# power_9v_rail.net
KiCad netlist of a schematic drawn in EAGLE
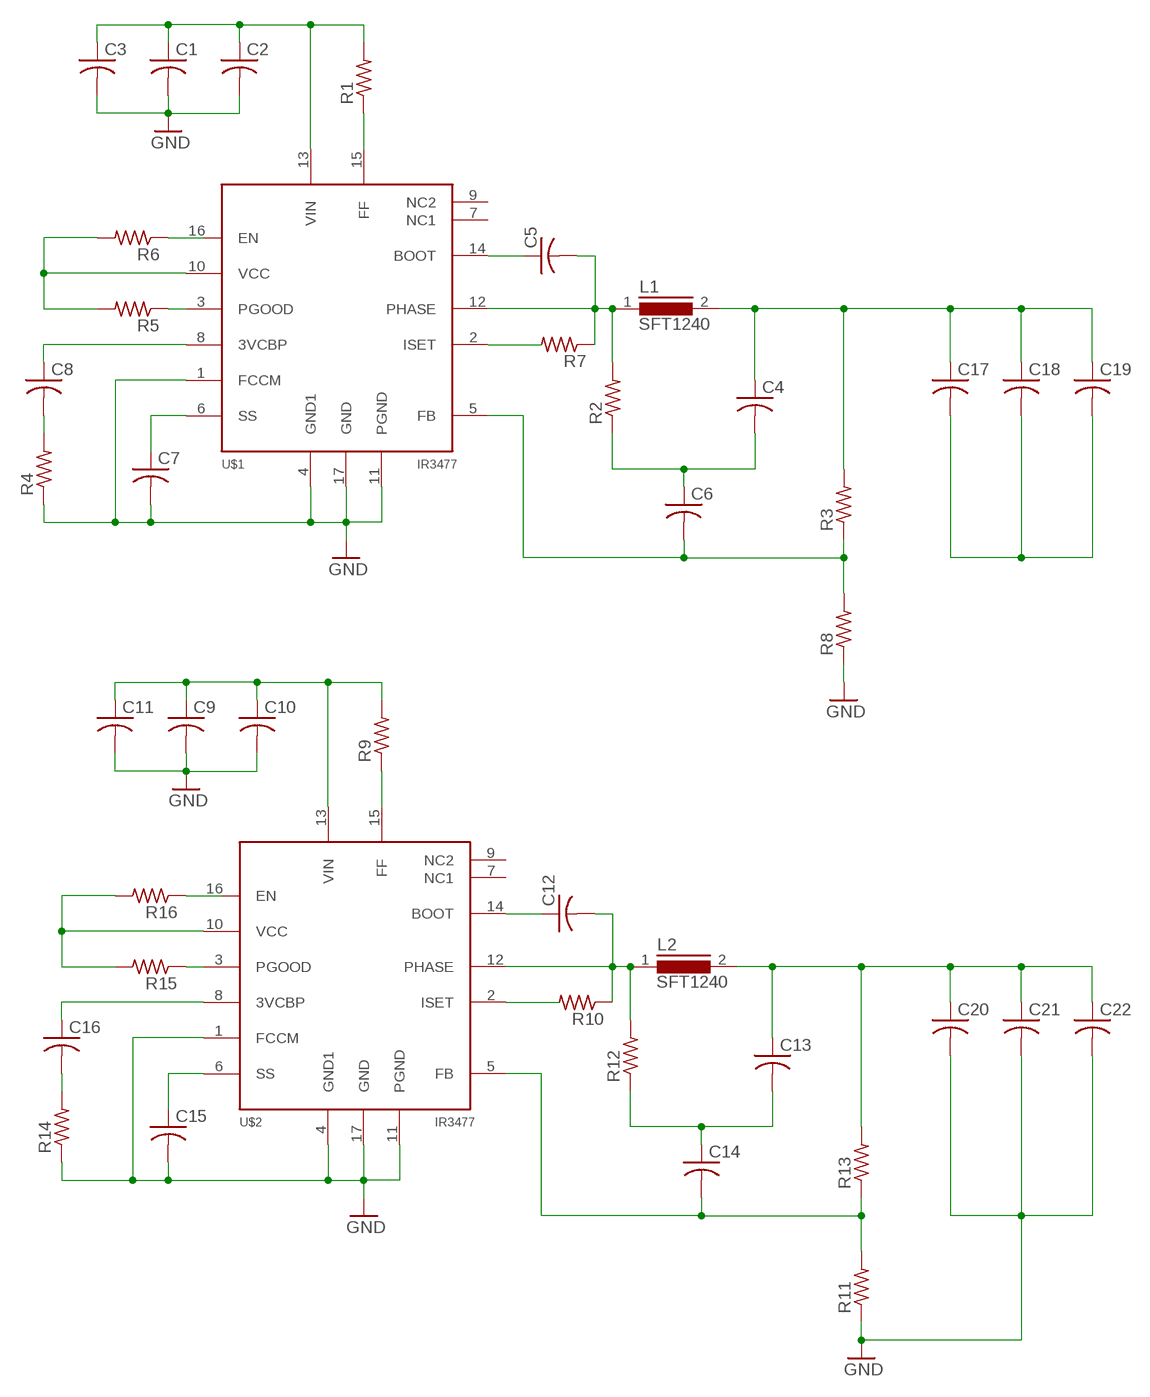
[diagram p0: schematic, sheet 1]

(export (version "E")
  (design (tool "Eeschema 10.0.6"))
  (components
    (comp (ref "C1")
      (value "C-USC0805K")
      (footprint "eagle-import:C0805K")
      (libsource (lib "eagle-import") (part "C-USC0805K"))
    )
    (comp (ref "C2")
      (value "C-USC0805K")
      (footprint "eagle-import:C0805K")
      (libsource (lib "eagle-import") (part "C-USC0805K"))
    )
    (comp (ref "C3")
      (value "C-USC0805K")
      (footprint "eagle-import:C0805K")
      (libsource (lib "eagle-import") (part "C-USC0805K"))
    )
    (comp (ref "C4")
      (value "C-USC0805K")
      (footprint "eagle-import:C0805K")
      (libsource (lib "eagle-import") (part "C-USC0805K"))
    )
    (comp (ref "C5")
      (value "C-USC0805K")
      (footprint "eagle-import:C0805K")
      (libsource (lib "eagle-import") (part "C-USC0805K"))
    )
    (comp (ref "C6")
      (value "C-USC0805K")
      (footprint "eagle-import:C0805K")
      (libsource (lib "eagle-import") (part "C-USC0805K"))
    )
    (comp (ref "C7")
      (value "C-USC0805K")
      (footprint "eagle-import:C0805K")
      (libsource (lib "eagle-import") (part "C-USC0805K"))
    )
    (comp (ref "C8")
      (value "C-USC0805K")
      (footprint "eagle-import:C0805K")
      (libsource (lib "eagle-import") (part "C-USC0805K"))
    )
    (comp (ref "C9")
      (value "C-USC0805K")
      (footprint "eagle-import:C0805K")
      (libsource (lib "eagle-import") (part "C-USC0805K"))
    )
    (comp (ref "C10")
      (value "C-USC0805K")
      (footprint "eagle-import:C0805K")
      (libsource (lib "eagle-import") (part "C-USC0805K"))
    )
    (comp (ref "C11")
      (value "C-USC0805K")
      (footprint "eagle-import:C0805K")
      (libsource (lib "eagle-import") (part "C-USC0805K"))
    )
    (comp (ref "C12")
      (value "C-USC0805K")
      (footprint "eagle-import:C0805K")
      (libsource (lib "eagle-import") (part "C-USC0805K"))
    )
    (comp (ref "C13")
      (value "C-USC0805K")
      (footprint "eagle-import:C0805K")
      (libsource (lib "eagle-import") (part "C-USC0805K"))
    )
    (comp (ref "C14")
      (value "C-USC0805K")
      (footprint "eagle-import:C0805K")
      (libsource (lib "eagle-import") (part "C-USC0805K"))
    )
    (comp (ref "C15")
      (value "C-USC0805K")
      (footprint "eagle-import:C0805K")
      (libsource (lib "eagle-import") (part "C-USC0805K"))
    )
    (comp (ref "C16")
      (value "C-USC0805K")
      (footprint "eagle-import:C0805K")
      (libsource (lib "eagle-import") (part "C-USC0805K"))
    )
    (comp (ref "C17")
      (value "C-USC0805K")
      (footprint "eagle-import:C0805K")
      (libsource (lib "eagle-import") (part "C-USC0805K"))
    )
    (comp (ref "C18")
      (value "C-USC0805K")
      (footprint "eagle-import:C0805K")
      (libsource (lib "eagle-import") (part "C-USC0805K"))
    )
    (comp (ref "C19")
      (value "C-USC0805K")
      (footprint "eagle-import:C0805K")
      (libsource (lib "eagle-import") (part "C-USC0805K"))
    )
    (comp (ref "C20")
      (value "C-USC0805K")
      (footprint "eagle-import:C0805K")
      (libsource (lib "eagle-import") (part "C-USC0805K"))
    )
    (comp (ref "C21")
      (value "C-USC0805K")
      (footprint "eagle-import:C0805K")
      (libsource (lib "eagle-import") (part "C-USC0805K"))
    )
    (comp (ref "C22")
      (value "C-USC0805K")
      (footprint "eagle-import:C0805K")
      (libsource (lib "eagle-import") (part "C-USC0805K"))
    )
    (comp (ref "L1")
      (value "SFT1240")
      (footprint "eagle-import:SFT1240")
      (libsource (lib "eagle-import") (part "SFT1240"))
    )
    (comp (ref "L2")
      (value "SFT1240")
      (footprint "eagle-import:SFT1240")
      (libsource (lib "eagle-import") (part "SFT1240"))
    )
    (comp (ref "R1")
      (value "R-US_R0805")
      (footprint "eagle-import:R0805")
      (libsource (lib "eagle-import") (part "R-US_R0805"))
    )
    (comp (ref "R2")
      (value "R-US_R0805")
      (footprint "eagle-import:R0805")
      (libsource (lib "eagle-import") (part "R-US_R0805"))
    )
    (comp (ref "R3")
      (value "R-US_R0805")
      (footprint "eagle-import:R0805")
      (libsource (lib "eagle-import") (part "R-US_R0805"))
    )
    (comp (ref "R4")
      (value "R-US_R0805")
      (footprint "eagle-import:R0805")
      (libsource (lib "eagle-import") (part "R-US_R0805"))
    )
    (comp (ref "R5")
      (value "R-US_R0805")
      (footprint "eagle-import:R0805")
      (libsource (lib "eagle-import") (part "R-US_R0805"))
    )
    (comp (ref "R6")
      (value "R-US_R0805")
      (footprint "eagle-import:R0805")
      (libsource (lib "eagle-import") (part "R-US_R0805"))
    )
    (comp (ref "R7")
      (value "R-US_R0805")
      (footprint "eagle-import:R0805")
      (libsource (lib "eagle-import") (part "R-US_R0805"))
    )
    (comp (ref "R8")
      (value "R-US_R0805")
      (footprint "eagle-import:R0805")
      (libsource (lib "eagle-import") (part "R-US_R0805"))
    )
    (comp (ref "R9")
      (value "R-US_R0805")
      (footprint "eagle-import:R0805")
      (libsource (lib "eagle-import") (part "R-US_R0805"))
    )
    (comp (ref "R10")
      (value "R-US_R0805")
      (footprint "eagle-import:R0805")
      (libsource (lib "eagle-import") (part "R-US_R0805"))
    )
    (comp (ref "R11")
      (value "R-US_R0805")
      (footprint "eagle-import:R0805")
      (libsource (lib "eagle-import") (part "R-US_R0805"))
    )
    (comp (ref "R12")
      (value "R-US_R0805")
      (footprint "eagle-import:R0805")
      (libsource (lib "eagle-import") (part "R-US_R0805"))
    )
    (comp (ref "R13")
      (value "R-US_R0805")
      (footprint "eagle-import:R0805")
      (libsource (lib "eagle-import") (part "R-US_R0805"))
    )
    (comp (ref "R14")
      (value "R-US_R0805")
      (footprint "eagle-import:R0805")
      (libsource (lib "eagle-import") (part "R-US_R0805"))
    )
    (comp (ref "R15")
      (value "R-US_R0805")
      (footprint "eagle-import:R0805")
      (libsource (lib "eagle-import") (part "R-US_R0805"))
    )
    (comp (ref "R16")
      (value "R-US_R0805")
      (footprint "eagle-import:R0805")
      (libsource (lib "eagle-import") (part "R-US_R0805"))
    )
    (comp (ref "U$1")
      (value "IC-1R34477-SMP")
      (footprint "eagle-import:IC-IR3477-SM")
      (libsource (lib "eagle-import") (part "IC-1R34477-SMP"))
    )
    (comp (ref "U$2")
      (value "IC-1R34477-SMP")
      (footprint "eagle-import:IC-IR3477-SM")
      (libsource (lib "eagle-import") (part "IC-1R34477-SMP"))
    )
  )
  (nets
    (net (code "1") (name "GND") (class "Default")
      (node (ref "C1") (pin "2") (pinfunction "2_2") (pintype "passive"))
      (node (ref "C10") (pin "2") (pinfunction "2_2") (pintype "passive"))
      (node (ref "C11") (pin "2") (pinfunction "2_2") (pintype "passive"))
      (node (ref "C15") (pin "2") (pinfunction "2_2") (pintype "passive"))
      (node (ref "C2") (pin "2") (pinfunction "2_2") (pintype "passive"))
      (node (ref "C20") (pin "2") (pinfunction "2_2") (pintype "passive"))
      (node (ref "C21") (pin "2") (pinfunction "2_2") (pintype "passive"))
      (node (ref "C22") (pin "2") (pinfunction "2_2") (pintype "passive"))
      (node (ref "C3") (pin "2") (pinfunction "2_2") (pintype "passive"))
      (node (ref "C7") (pin "2") (pinfunction "2_2") (pintype "passive"))
      (node (ref "C9") (pin "2") (pinfunction "2_2") (pintype "passive"))
      (node (ref "R11") (pin "1") (pinfunction "1_1") (pintype "passive"))
      (node (ref "R14") (pin "1") (pinfunction "1_1") (pintype "passive"))
      (node (ref "R4") (pin "1") (pinfunction "1_1") (pintype "passive"))
      (node (ref "R8") (pin "1") (pinfunction "1_1") (pintype "passive"))
      (node (ref "U$1") (pin "1") (pinfunction "FCCM_1") (pintype "bidirectional"))
      (node (ref "U$1") (pin "11") (pinfunction "PGND_11") (pintype "bidirectional"))
      (node (ref "U$1") (pin "17") (pinfunction "GND_17") (pintype "bidirectional"))
      (node (ref "U$1") (pin "4") (pinfunction "GND1_4") (pintype "bidirectional"))
      (node (ref "U$2") (pin "1") (pinfunction "FCCM_1") (pintype "bidirectional"))
      (node (ref "U$2") (pin "11") (pinfunction "PGND_11") (pintype "bidirectional"))
      (node (ref "U$2") (pin "17") (pinfunction "GND_17") (pintype "bidirectional"))
      (node (ref "U$2") (pin "4") (pinfunction "GND1_4") (pintype "bidirectional"))
    )
    (net (code "2") (name "Net-(C4-Pad2)") (class "Default")
      (node (ref "C4") (pin "2") (pinfunction "2_2") (pintype "passive"))
      (node (ref "C6") (pin "1") (pinfunction "1_1") (pintype "passive"))
      (node (ref "R2") (pin "1") (pinfunction "1_1") (pintype "passive"))
    )
    (net (code "3") (name "Net-(C8-Pad2)") (class "Default")
      (node (ref "C8") (pin "2") (pinfunction "2_2") (pintype "passive"))
      (node (ref "R4") (pin "2") (pinfunction "2_2") (pintype "passive"))
    )
    (net (code "4") (name "Net-(C13-Pad1)") (class "Default")
      (node (ref "C13") (pin "1") (pinfunction "1_1") (pintype "passive"))
      (node (ref "C20") (pin "1") (pinfunction "1_1") (pintype "passive"))
      (node (ref "C21") (pin "1") (pinfunction "1_1") (pintype "passive"))
      (node (ref "C22") (pin "1") (pinfunction "1_1") (pintype "passive"))
      (node (ref "L2") (pin "2") (pinfunction "2_2") (pintype "passive"))
      (node (ref "R13") (pin "2") (pinfunction "2_2") (pintype "passive"))
    )
    (net (code "5") (name "Net-(C13-Pad2)") (class "Default")
      (node (ref "C13") (pin "2") (pinfunction "2_2") (pintype "passive"))
      (node (ref "C14") (pin "1") (pinfunction "1_1") (pintype "passive"))
      (node (ref "R12") (pin "1") (pinfunction "1_1") (pintype "passive"))
    )
    (net (code "6") (name "Net-(C16-Pad2)") (class "Default")
      (node (ref "C16") (pin "2") (pinfunction "2_2") (pintype "passive"))
      (node (ref "R14") (pin "2") (pinfunction "2_2") (pintype "passive"))
    )
    (net (code "7") (name "Net-(C17-Pad1)") (class "Default")
      (node (ref "C17") (pin "1") (pinfunction "1_1") (pintype "passive"))
      (node (ref "C18") (pin "1") (pinfunction "1_1") (pintype "passive"))
      (node (ref "C19") (pin "1") (pinfunction "1_1") (pintype "passive"))
      (node (ref "C4") (pin "1") (pinfunction "1_1") (pintype "passive"))
      (node (ref "L1") (pin "2") (pinfunction "2_2") (pintype "passive"))
      (node (ref "R3") (pin "2") (pinfunction "2_2") (pintype "passive"))
    )
    (net (code "8") (name "Net-(C17-Pad2)") (class "Default")
      (node (ref "C17") (pin "2") (pinfunction "2_2") (pintype "passive"))
      (node (ref "C18") (pin "2") (pinfunction "2_2") (pintype "passive"))
      (node (ref "C19") (pin "2") (pinfunction "2_2") (pintype "passive"))
    )
    (net (code "9") (name "Net-(U$1-3VCBP)") (class "Default")
      (node (ref "C8") (pin "1") (pinfunction "1_1") (pintype "passive"))
      (node (ref "U$1") (pin "8") (pinfunction "3VCBP_8") (pintype "bidirectional"))
    )
    (net (code "10") (name "Net-(U$1-BOOT)") (class "Default")
      (node (ref "C5") (pin "1") (pinfunction "1_1") (pintype "passive"))
      (node (ref "U$1") (pin "14") (pinfunction "BOOT_14") (pintype "bidirectional"))
    )
    (net (code "11") (name "Net-(U$1-FB)") (class "Default")
      (node (ref "C6") (pin "2") (pinfunction "2_2") (pintype "passive"))
      (node (ref "R3") (pin "1") (pinfunction "1_1") (pintype "passive"))
      (node (ref "R8") (pin "2") (pinfunction "2_2") (pintype "passive"))
      (node (ref "U$1") (pin "5") (pinfunction "FB_5") (pintype "bidirectional"))
    )
    (net (code "12") (name "Net-(U$1-FF)") (class "Default")
      (node (ref "R1") (pin "1") (pinfunction "1_1") (pintype "passive"))
      (node (ref "U$1") (pin "15") (pinfunction "FF_15") (pintype "bidirectional"))
    )
    (net (code "13") (name "Net-(U$1-PGOOD)") (class "Default")
      (node (ref "R5") (pin "1") (pinfunction "1_1") (pintype "passive"))
      (node (ref "U$1") (pin "3") (pinfunction "PGOOD_3") (pintype "bidirectional"))
    )
    (net (code "14") (name "Net-(U$1-PHASE)") (class "Default")
      (node (ref "C5") (pin "2") (pinfunction "2_2") (pintype "passive"))
      (node (ref "L1") (pin "1") (pinfunction "1_1") (pintype "passive"))
      (node (ref "R2") (pin "2") (pinfunction "2_2") (pintype "passive"))
      (node (ref "R7") (pin "1") (pinfunction "1_1") (pintype "passive"))
      (node (ref "U$1") (pin "12") (pinfunction "PHASE_12") (pintype "bidirectional"))
    )
    (net (code "15") (name "Net-(U$1-SS)") (class "Default")
      (node (ref "C7") (pin "1") (pinfunction "1_1") (pintype "passive"))
      (node (ref "U$1") (pin "6") (pinfunction "SS_6") (pintype "bidirectional"))
    )
    (net (code "16") (name "Net-(U$1-VCC)") (class "Default")
      (node (ref "R5") (pin "2") (pinfunction "2_2") (pintype "passive"))
      (node (ref "R6") (pin "2") (pinfunction "2_2") (pintype "passive"))
      (node (ref "U$1") (pin "10") (pinfunction "VCC_10") (pintype "bidirectional"))
    )
    (net (code "17") (name "Net-(U$1-VIN)") (class "Default")
      (node (ref "C1") (pin "1") (pinfunction "1_1") (pintype "passive"))
      (node (ref "C2") (pin "1") (pinfunction "1_1") (pintype "passive"))
      (node (ref "C3") (pin "1") (pinfunction "1_1") (pintype "passive"))
      (node (ref "R1") (pin "2") (pinfunction "2_2") (pintype "passive"))
      (node (ref "U$1") (pin "13") (pinfunction "VIN_13") (pintype "bidirectional"))
    )
    (net (code "18") (name "Net-(U$2-3VCBP)") (class "Default")
      (node (ref "C16") (pin "1") (pinfunction "1_1") (pintype "passive"))
      (node (ref "U$2") (pin "8") (pinfunction "3VCBP_8") (pintype "bidirectional"))
    )
    (net (code "19") (name "Net-(U$2-BOOT)") (class "Default")
      (node (ref "C12") (pin "1") (pinfunction "1_1") (pintype "passive"))
      (node (ref "U$2") (pin "14") (pinfunction "BOOT_14") (pintype "bidirectional"))
    )
    (net (code "20") (name "Net-(U$2-FB)") (class "Default")
      (node (ref "C14") (pin "2") (pinfunction "2_2") (pintype "passive"))
      (node (ref "R11") (pin "2") (pinfunction "2_2") (pintype "passive"))
      (node (ref "R13") (pin "1") (pinfunction "1_1") (pintype "passive"))
      (node (ref "U$2") (pin "5") (pinfunction "FB_5") (pintype "bidirectional"))
    )
    (net (code "21") (name "Net-(U$2-FF)") (class "Default")
      (node (ref "R9") (pin "1") (pinfunction "1_1") (pintype "passive"))
      (node (ref "U$2") (pin "15") (pinfunction "FF_15") (pintype "bidirectional"))
    )
    (net (code "22") (name "Net-(U$2-PGOOD)") (class "Default")
      (node (ref "R15") (pin "1") (pinfunction "1_1") (pintype "passive"))
      (node (ref "U$2") (pin "3") (pinfunction "PGOOD_3") (pintype "bidirectional"))
    )
    (net (code "23") (name "Net-(U$2-PHASE)") (class "Default")
      (node (ref "C12") (pin "2") (pinfunction "2_2") (pintype "passive"))
      (node (ref "L2") (pin "1") (pinfunction "1_1") (pintype "passive"))
      (node (ref "R10") (pin "1") (pinfunction "1_1") (pintype "passive"))
      (node (ref "R12") (pin "2") (pinfunction "2_2") (pintype "passive"))
      (node (ref "U$2") (pin "12") (pinfunction "PHASE_12") (pintype "bidirectional"))
    )
    (net (code "24") (name "Net-(U$2-SS)") (class "Default")
      (node (ref "C15") (pin "1") (pinfunction "1_1") (pintype "passive"))
      (node (ref "U$2") (pin "6") (pinfunction "SS_6") (pintype "bidirectional"))
    )
    (net (code "25") (name "Net-(U$2-VCC)") (class "Default")
      (node (ref "R15") (pin "2") (pinfunction "2_2") (pintype "passive"))
      (node (ref "R16") (pin "2") (pinfunction "2_2") (pintype "passive"))
      (node (ref "U$2") (pin "10") (pinfunction "VCC_10") (pintype "bidirectional"))
    )
    (net (code "26") (name "Net-(U$2-VIN)") (class "Default")
      (node (ref "C10") (pin "1") (pinfunction "1_1") (pintype "passive"))
      (node (ref "C11") (pin "1") (pinfunction "1_1") (pintype "passive"))
      (node (ref "C9") (pin "1") (pinfunction "1_1") (pintype "passive"))
      (node (ref "R9") (pin "2") (pinfunction "2_2") (pintype "passive"))
      (node (ref "U$2") (pin "13") (pinfunction "VIN_13") (pintype "bidirectional"))
    )
    (net (code "27") (name "unconnected-(R6-Pad1)") (class "Default")
      (node (ref "R6") (pin "1") (pinfunction "1_1") (pintype "passive"))
    )
    (net (code "28") (name "unconnected-(R7-Pad2)") (class "Default")
      (node (ref "R7") (pin "2") (pinfunction "2_2") (pintype "passive"))
    )
    (net (code "29") (name "unconnected-(R10-Pad2)") (class "Default")
      (node (ref "R10") (pin "2") (pinfunction "2_2") (pintype "passive"))
    )
    (net (code "30") (name "unconnected-(R16-Pad1)") (class "Default")
      (node (ref "R16") (pin "1") (pinfunction "1_1") (pintype "passive"))
    )
    (net (code "31") (name "unconnected-(U$1-EN-Pad16)") (class "Default")
      (node (ref "U$1") (pin "16") (pinfunction "EN_16") (pintype "bidirectional"))
    )
    (net (code "32") (name "unconnected-(U$1-ISET-Pad2)") (class "Default")
      (node (ref "U$1") (pin "2") (pinfunction "ISET_2") (pintype "bidirectional"))
    )
    (net (code "33") (name "unconnected-(U$1-NC1-Pad7)") (class "Default")
      (node (ref "U$1") (pin "7") (pinfunction "NC1_7") (pintype "bidirectional"))
    )
    (net (code "34") (name "unconnected-(U$1-NC2-Pad9)") (class "Default")
      (node (ref "U$1") (pin "9") (pinfunction "NC2_9") (pintype "bidirectional"))
    )
    (net (code "35") (name "unconnected-(U$2-EN-Pad16)") (class "Default")
      (node (ref "U$2") (pin "16") (pinfunction "EN_16") (pintype "bidirectional"))
    )
    (net (code "36") (name "unconnected-(U$2-ISET-Pad2)") (class "Default")
      (node (ref "U$2") (pin "2") (pinfunction "ISET_2") (pintype "bidirectional"))
    )
    (net (code "37") (name "unconnected-(U$2-NC1-Pad7)") (class "Default")
      (node (ref "U$2") (pin "7") (pinfunction "NC1_7") (pintype "bidirectional"))
    )
    (net (code "38") (name "unconnected-(U$2-NC2-Pad9)") (class "Default")
      (node (ref "U$2") (pin "9") (pinfunction "NC2_9") (pintype "bidirectional"))
    )
  )
)
